# RegisterB.net
KiCad netlist of a schematic drawn in Altium Designer
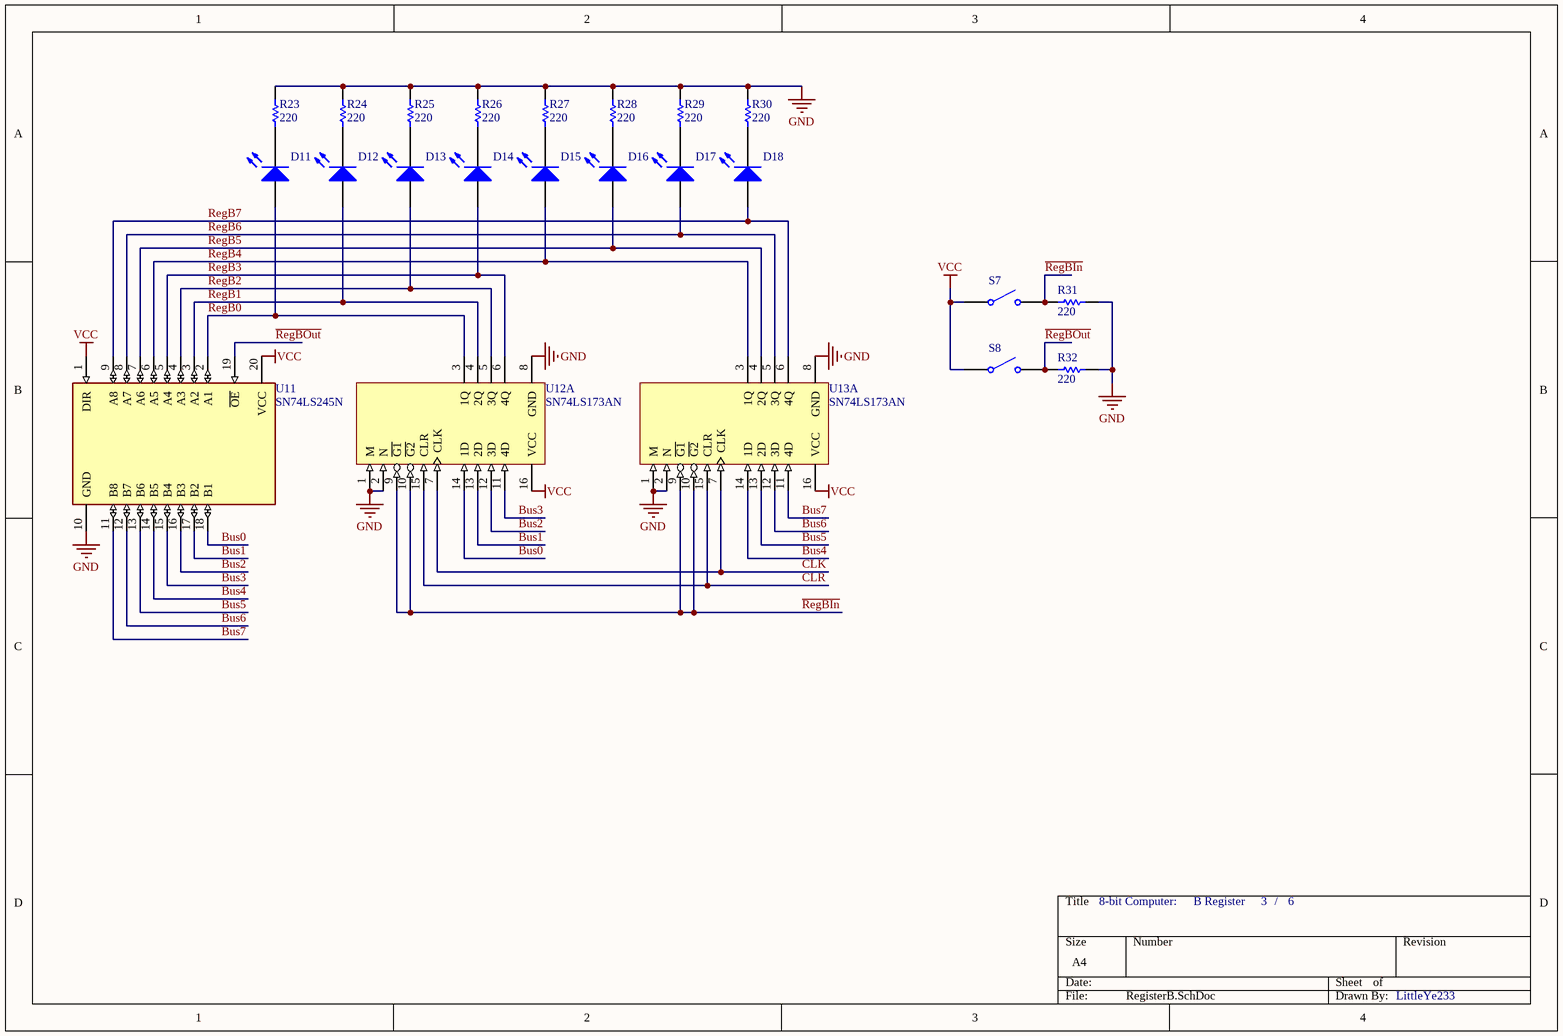
[diagram p0: RegisterB.SchDoc]

(export (version "E")
  (design (tool "Eeschema 10.0.6"))
  (components
    (comp (ref "D11")
      (value "Light-Emitting Diode")
      (libsource (lib "Simulation Generic Components") (part "LED"))
    )
    (comp (ref "D12")
      (value "Light-Emitting Diode")
      (libsource (lib "Simulation Generic Components") (part "LED"))
    )
    (comp (ref "D13")
      (value "Light-Emitting Diode")
      (libsource (lib "Simulation Generic Components") (part "LED"))
    )
    (comp (ref "D14")
      (value "Light-Emitting Diode")
      (libsource (lib "Simulation Generic Components") (part "LED"))
    )
    (comp (ref "D15")
      (value "Light-Emitting Diode")
      (libsource (lib "Simulation Generic Components") (part "LED"))
    )
    (comp (ref "D16")
      (value "Light-Emitting Diode")
      (libsource (lib "Simulation Generic Components") (part "LED"))
    )
    (comp (ref "D17")
      (value "Light-Emitting Diode")
      (libsource (lib "Simulation Generic Components") (part "LED"))
    )
    (comp (ref "D18")
      (value "Light-Emitting Diode")
      (libsource (lib "Simulation Generic Components") (part "LED"))
    )
    (comp (ref "R23")
      (value "220")
      (description "Resistor")
      (libsource (lib "Simulation Generic Components") (part "Resistor"))
    )
    (comp (ref "R24")
      (value "220")
      (description "Resistor")
      (libsource (lib "Simulation Generic Components") (part "Resistor"))
    )
    (comp (ref "R25")
      (value "220")
      (description "Resistor")
      (libsource (lib "Simulation Generic Components") (part "Resistor"))
    )
    (comp (ref "R26")
      (value "220")
      (description "Resistor")
      (libsource (lib "Simulation Generic Components") (part "Resistor"))
    )
    (comp (ref "R27")
      (value "220")
      (description "Resistor")
      (libsource (lib "Simulation Generic Components") (part "Resistor"))
    )
    (comp (ref "R28")
      (value "220")
      (description "Resistor")
      (libsource (lib "Simulation Generic Components") (part "Resistor"))
    )
    (comp (ref "R29")
      (value "220")
      (description "Resistor")
      (libsource (lib "Simulation Generic Components") (part "Resistor"))
    )
    (comp (ref "R30")
      (value "220")
      (description "Resistor")
      (libsource (lib "Simulation Generic Components") (part "Resistor"))
    )
    (comp (ref "R31")
      (value "220")
      (description "Resistor")
      (libsource (lib "Simulation Generic Components") (part "Resistor"))
    )
    (comp (ref "R32")
      (value "220")
      (description "Resistor")
      (libsource (lib "Simulation Generic Components") (part "Resistor"))
    )
    (comp (ref "S7")
      (value "Single-Pole, Single-Throw Switch")
      (libsource (lib "Simulation Generic Components") (part "SPST SW"))
    )
    (comp (ref "S8")
      (value "Single-Pole, Single-Throw Switch")
      (libsource (lib "Simulation Generic Components") (part "SPST SW"))
    )
    (comp (ref "U11")
      (value "SN74LS245N")
      (footprint "FP-N0020A-MFG")
      (description "IC TXRX NON-INVERT 5.25V 20DIP")
      (libsource (lib "SN74LS245N") (part "CMP-1620-00419-3"))
    )
    (comp (ref "U12")
      (value "SN74LS173AN")
      (footprint "N0016A")
      (description "4-Bit D-type Registers with 3-State Outputs, N0016A, TUBE")
      (fields
        (field (name "MANUFACTURER") "Texas Instruments")
        (field (name "GENERIC PART NUMBER") "SN74LS173A")
      )
      (libsource (lib "SN74LS173AN") (part "CMP-1619-00777-2"))
    )
    (comp (ref "U13")
      (value "SN74LS173AN")
      (footprint "N0016A")
      (description "4-Bit D-type Registers with 3-State Outputs, N0016A, TUBE")
      (fields
        (field (name "MANUFACTURER") "Texas Instruments")
        (field (name "GENERIC PART NUMBER") "SN74LS173A")
      )
      (libsource (lib "SN74LS173AN") (part "CMP-1619-00777-2"))
    )
  )
  (nets
    (net (code "1") (name "/Bus0") (class "Default")
      (node (ref "U11") (pin "18") (pinfunction "B1_18") (pintype "bidirectional"))
      (node (ref "U12") (pin "14") (pinfunction "1D_14") (pintype "input"))
    )
    (net (code "2") (name "/Bus1") (class "Default")
      (node (ref "U11") (pin "17") (pinfunction "B2_17") (pintype "bidirectional"))
      (node (ref "U12") (pin "13") (pinfunction "2D_13") (pintype "input"))
    )
    (net (code "3") (name "/Bus2") (class "Default")
      (node (ref "U11") (pin "16") (pinfunction "B3_16") (pintype "bidirectional"))
      (node (ref "U12") (pin "12") (pinfunction "3D_12") (pintype "input"))
    )
    (net (code "4") (name "/Bus3") (class "Default")
      (node (ref "U11") (pin "15") (pinfunction "B4_15") (pintype "bidirectional"))
      (node (ref "U12") (pin "11") (pinfunction "4D_11") (pintype "input"))
    )
    (net (code "5") (name "/Bus4") (class "Default")
      (node (ref "U11") (pin "14") (pinfunction "B5_14") (pintype "bidirectional"))
      (node (ref "U13") (pin "14") (pinfunction "1D_14") (pintype "input"))
    )
    (net (code "6") (name "/Bus5") (class "Default")
      (node (ref "U11") (pin "13") (pinfunction "B6_13") (pintype "bidirectional"))
      (node (ref "U13") (pin "13") (pinfunction "2D_13") (pintype "input"))
    )
    (net (code "7") (name "/Bus6") (class "Default")
      (node (ref "U11") (pin "12") (pinfunction "B7_12") (pintype "bidirectional"))
      (node (ref "U13") (pin "12") (pinfunction "3D_12") (pintype "input"))
    )
    (net (code "8") (name "/Bus7") (class "Default")
      (node (ref "U11") (pin "11") (pinfunction "B8_11") (pintype "bidirectional"))
      (node (ref "U13") (pin "11") (pinfunction "4D_11") (pintype "input"))
    )
    (net (code "9") (name "/CLK") (class "Default")
      (node (ref "U12") (pin "7") (pinfunction "CLK_7") (pintype "input"))
      (node (ref "U13") (pin "7") (pinfunction "CLK_7") (pintype "input"))
    )
    (net (code "10") (name "/CLR") (class "Default")
      (node (ref "U12") (pin "15") (pinfunction "CLR_15") (pintype "input"))
      (node (ref "U13") (pin "15") (pinfunction "CLR_15") (pintype "input"))
    )
    (net (code "11") (name "/RegB0") (class "Default")
      (node (ref "D11") (pin "1") (pinfunction "A_1") (pintype "passive"))
      (node (ref "U11") (pin "2") (pinfunction "A1_2") (pintype "bidirectional"))
      (node (ref "U12") (pin "3") (pinfunction "1Q_3") (pintype "tri_state"))
    )
    (net (code "12") (name "/RegB1") (class "Default")
      (node (ref "D12") (pin "1") (pinfunction "A_1") (pintype "passive"))
      (node (ref "U11") (pin "3") (pinfunction "A2_3") (pintype "bidirectional"))
      (node (ref "U12") (pin "4") (pinfunction "2Q_4") (pintype "tri_state"))
    )
    (net (code "13") (name "/RegB2") (class "Default")
      (node (ref "D13") (pin "1") (pinfunction "A_1") (pintype "passive"))
      (node (ref "U11") (pin "4") (pinfunction "A3_4") (pintype "bidirectional"))
      (node (ref "U12") (pin "5") (pinfunction "3Q_5") (pintype "tri_state"))
    )
    (net (code "14") (name "/RegB3") (class "Default")
      (node (ref "D14") (pin "1") (pinfunction "A_1") (pintype "passive"))
      (node (ref "U11") (pin "5") (pinfunction "A4_5") (pintype "bidirectional"))
      (node (ref "U12") (pin "6") (pinfunction "4Q_6") (pintype "tri_state"))
    )
    (net (code "15") (name "/RegB4") (class "Default")
      (node (ref "D15") (pin "1") (pinfunction "A_1") (pintype "passive"))
      (node (ref "U11") (pin "6") (pinfunction "A5_6") (pintype "bidirectional"))
      (node (ref "U13") (pin "3") (pinfunction "1Q_3") (pintype "tri_state"))
    )
    (net (code "16") (name "/RegB5") (class "Default")
      (node (ref "D16") (pin "1") (pinfunction "A_1") (pintype "passive"))
      (node (ref "U11") (pin "7") (pinfunction "A6_7") (pintype "bidirectional"))
      (node (ref "U13") (pin "4") (pinfunction "2Q_4") (pintype "tri_state"))
    )
    (net (code "17") (name "/RegB6") (class "Default")
      (node (ref "D17") (pin "1") (pinfunction "A_1") (pintype "passive"))
      (node (ref "U11") (pin "8") (pinfunction "A7_8") (pintype "bidirectional"))
      (node (ref "U13") (pin "5") (pinfunction "3Q_5") (pintype "tri_state"))
    )
    (net (code "18") (name "/RegB7") (class "Default")
      (node (ref "D18") (pin "1") (pinfunction "A_1") (pintype "passive"))
      (node (ref "U11") (pin "9") (pinfunction "A8_9") (pintype "bidirectional"))
      (node (ref "U13") (pin "6") (pinfunction "4Q_6") (pintype "tri_state"))
    )
    (net (code "19") (name "/~{RegBIn}") (class "Default")
      (node (ref "R31") (pin "2") (pinfunction "2_2") (pintype "passive"))
      (node (ref "S7") (pin "2") (pinfunction "2_2") (pintype "passive"))
      (node (ref "U12") (pin "10") (pinfunction "~{G2}_10") (pintype "input"))
      (node (ref "U12") (pin "9") (pinfunction "~{G1}_9") (pintype "input"))
      (node (ref "U13") (pin "10") (pinfunction "~{G2}_10") (pintype "input"))
      (node (ref "U13") (pin "9") (pinfunction "~{G1}_9") (pintype "input"))
    )
    (net (code "20") (name "/~{RegBOut}") (class "Default")
      (node (ref "R32") (pin "2") (pinfunction "2_2") (pintype "passive"))
      (node (ref "S8") (pin "2") (pinfunction "2_2") (pintype "passive"))
      (node (ref "U11") (pin "19") (pinfunction "~{OE}_19") (pintype "input"))
    )
    (net (code "21") (name "GND") (class "Default")
      (node (ref "R23") (pin "2") (pinfunction "2_2") (pintype "passive"))
      (node (ref "R24") (pin "2") (pinfunction "2_2") (pintype "passive"))
      (node (ref "R25") (pin "2") (pinfunction "2_2") (pintype "passive"))
      (node (ref "R26") (pin "2") (pinfunction "2_2") (pintype "passive"))
      (node (ref "R27") (pin "2") (pinfunction "2_2") (pintype "passive"))
      (node (ref "R28") (pin "2") (pinfunction "2_2") (pintype "passive"))
      (node (ref "R29") (pin "2") (pinfunction "2_2") (pintype "passive"))
      (node (ref "R30") (pin "2") (pinfunction "2_2") (pintype "passive"))
      (node (ref "R31") (pin "1") (pinfunction "1_1") (pintype "passive"))
      (node (ref "R32") (pin "1") (pinfunction "1_1") (pintype "passive"))
      (node (ref "U11") (pin "10") (pinfunction "GND_10") (pintype "power_in"))
      (node (ref "U12") (pin "1") (pinfunction "M_1") (pintype "input"))
      (node (ref "U12") (pin "2") (pinfunction "N_2") (pintype "input"))
      (node (ref "U12") (pin "8") (pinfunction "GND_8") (pintype "power_in"))
      (node (ref "U13") (pin "1") (pinfunction "M_1") (pintype "input"))
      (node (ref "U13") (pin "2") (pinfunction "N_2") (pintype "input"))
      (node (ref "U13") (pin "8") (pinfunction "GND_8") (pintype "power_in"))
    )
    (net (code "22") (name "Net-(D11-K)") (class "Default")
      (node (ref "D11") (pin "2") (pinfunction "K_2") (pintype "passive"))
      (node (ref "R23") (pin "1") (pinfunction "1_1") (pintype "passive"))
    )
    (net (code "23") (name "Net-(D12-K)") (class "Default")
      (node (ref "D12") (pin "2") (pinfunction "K_2") (pintype "passive"))
      (node (ref "R24") (pin "1") (pinfunction "1_1") (pintype "passive"))
    )
    (net (code "24") (name "Net-(D13-K)") (class "Default")
      (node (ref "D13") (pin "2") (pinfunction "K_2") (pintype "passive"))
      (node (ref "R25") (pin "1") (pinfunction "1_1") (pintype "passive"))
    )
    (net (code "25") (name "Net-(D14-K)") (class "Default")
      (node (ref "D14") (pin "2") (pinfunction "K_2") (pintype "passive"))
      (node (ref "R26") (pin "1") (pinfunction "1_1") (pintype "passive"))
    )
    (net (code "26") (name "Net-(D15-K)") (class "Default")
      (node (ref "D15") (pin "2") (pinfunction "K_2") (pintype "passive"))
      (node (ref "R27") (pin "1") (pinfunction "1_1") (pintype "passive"))
    )
    (net (code "27") (name "Net-(D16-K)") (class "Default")
      (node (ref "D16") (pin "2") (pinfunction "K_2") (pintype "passive"))
      (node (ref "R28") (pin "1") (pinfunction "1_1") (pintype "passive"))
    )
    (net (code "28") (name "Net-(D17-K)") (class "Default")
      (node (ref "D17") (pin "2") (pinfunction "K_2") (pintype "passive"))
      (node (ref "R29") (pin "1") (pinfunction "1_1") (pintype "passive"))
    )
    (net (code "29") (name "Net-(D18-K)") (class "Default")
      (node (ref "D18") (pin "2") (pinfunction "K_2") (pintype "passive"))
      (node (ref "R30") (pin "1") (pinfunction "1_1") (pintype "passive"))
    )
    (net (code "30") (name "VCC") (class "Default")
      (node (ref "S7") (pin "1") (pinfunction "1_1") (pintype "passive"))
      (node (ref "S8") (pin "1") (pinfunction "1_1") (pintype "passive"))
      (node (ref "U11") (pin "1") (pinfunction "DIR_1") (pintype "input"))
      (node (ref "U11") (pin "20") (pinfunction "VCC_20") (pintype "power_in"))
      (node (ref "U12") (pin "16") (pinfunction "VCC_16") (pintype "power_in"))
      (node (ref "U13") (pin "16") (pinfunction "VCC_16") (pintype "power_in"))
    )
  )
)
